# vl822.net
KiCad netlist of a schematic drawn in Altium Designer
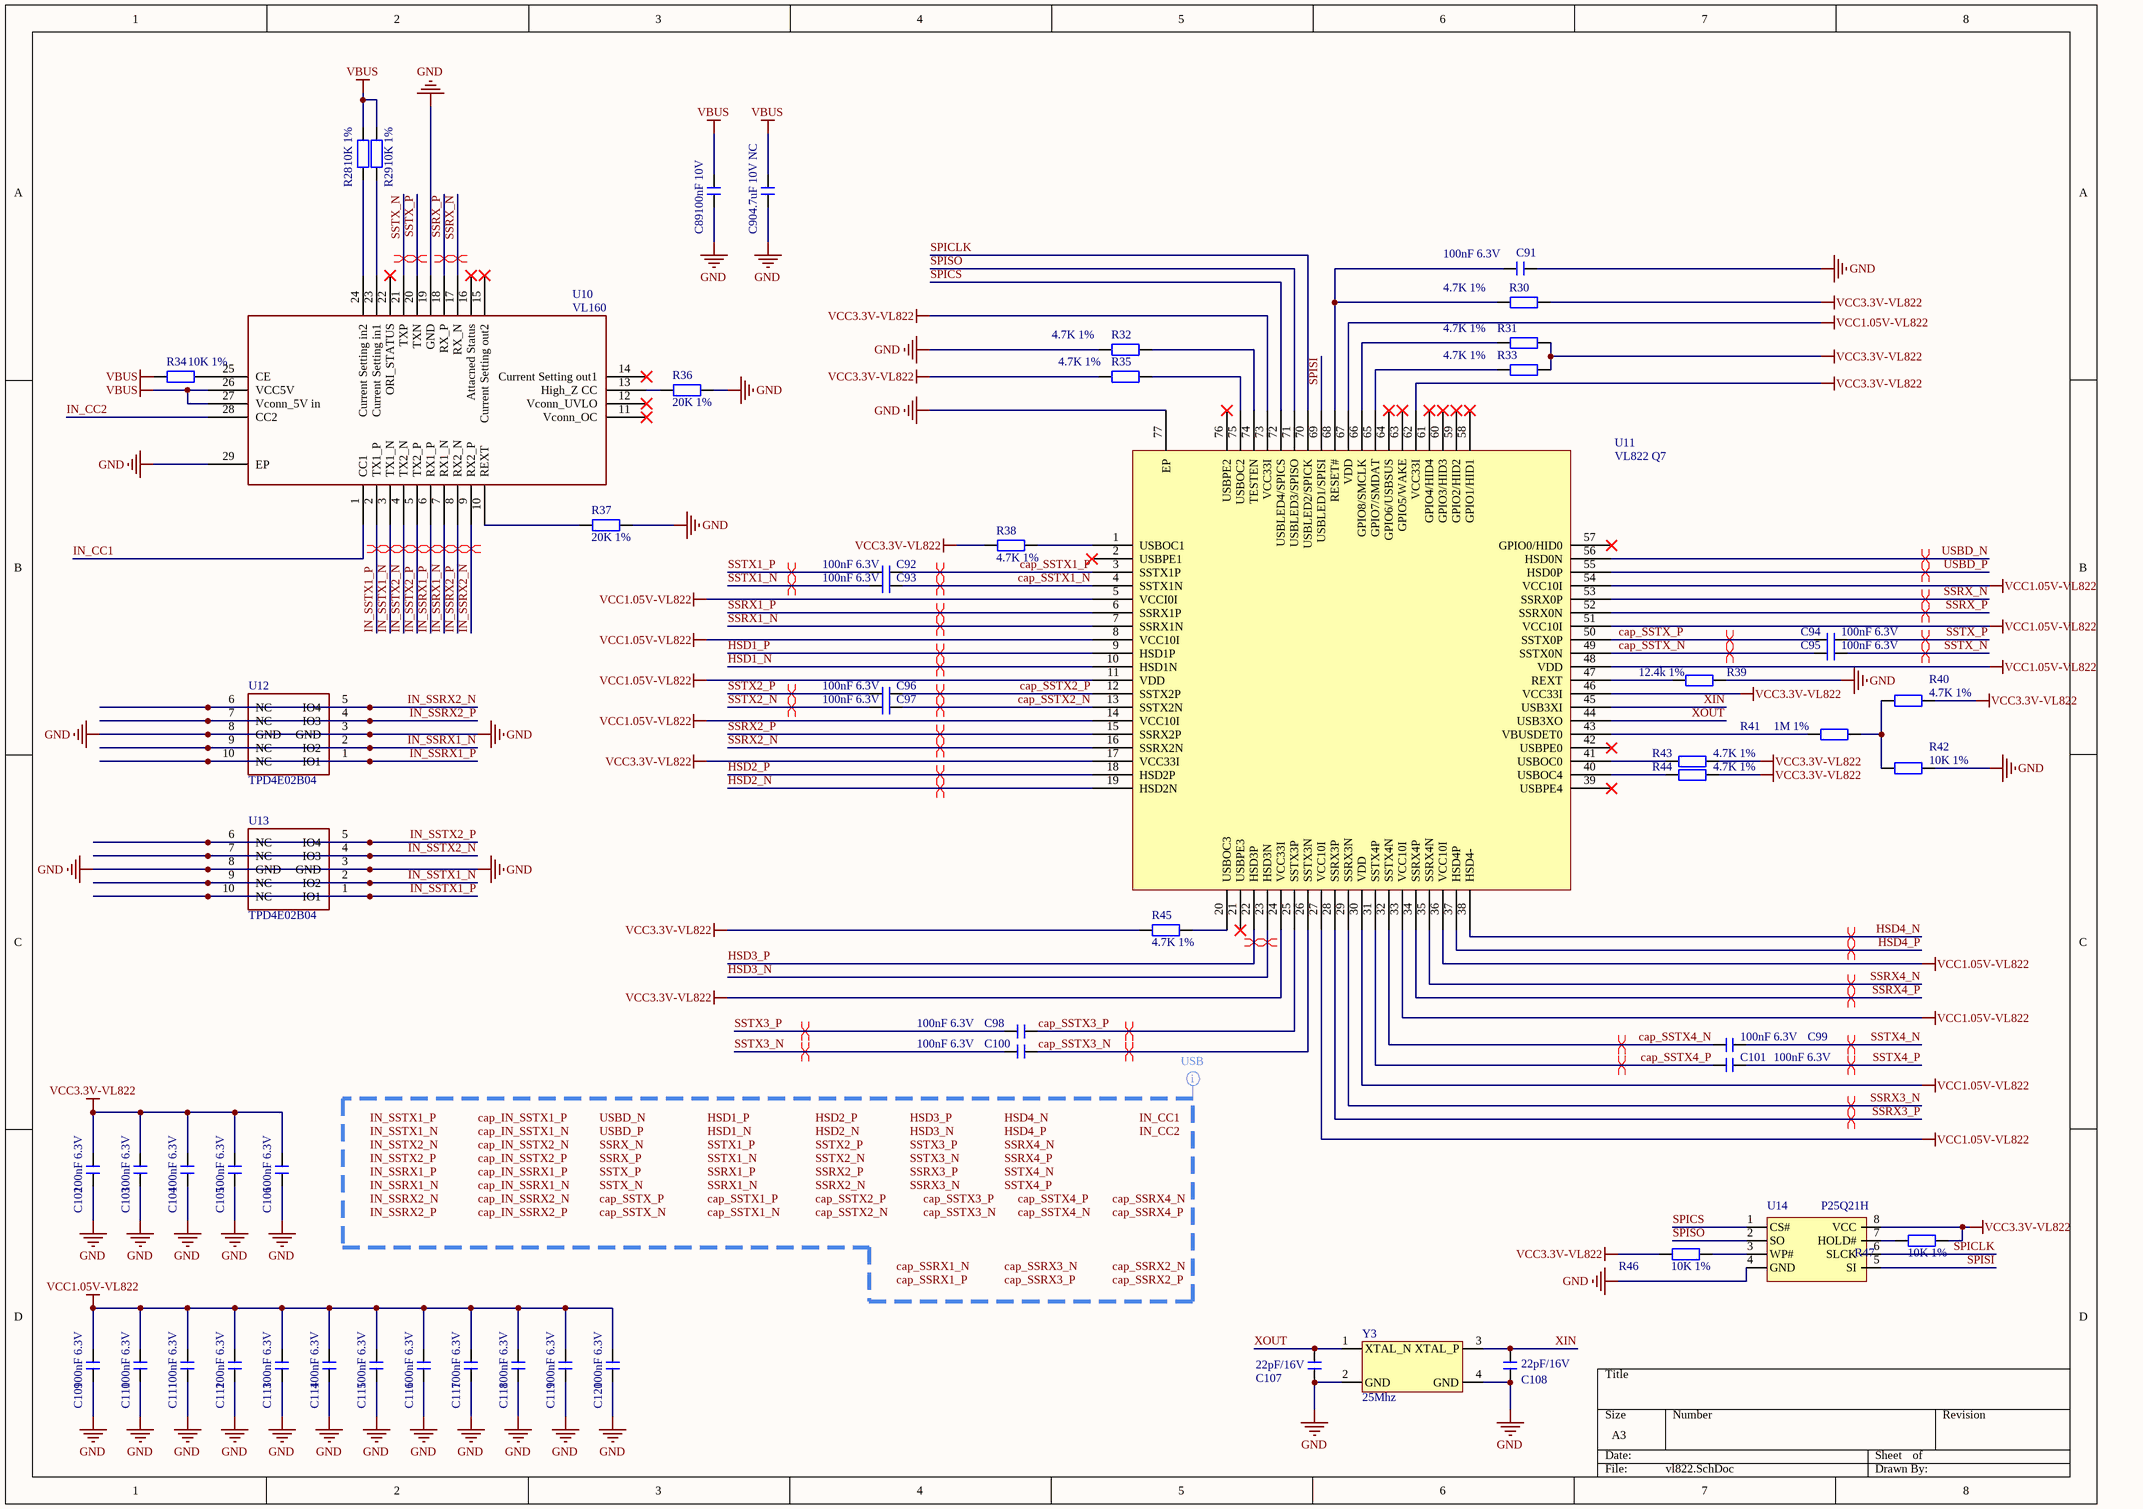
[diagram p0: vl822.SchDoc]

(export (version "E")
  (design (tool "Eeschema 10.0.6"))
  (components
    (comp (ref "C89")
      (value "100nF 10V")
      (footprint "C0402_L")
      (description "无极性贴片电容")
      (fields (field (name "版权归属") "源创客"))
      (libsource (lib "Capacitor") (part "C"))
    )
    (comp (ref "C90")
      (value "4.7uF 10V NC")
      (footprint "C0402_L")
      (description "无极性贴片电容")
      (fields (field (name "版权归属") "源创客"))
      (libsource (lib "Capacitor") (part "C"))
    )
    (comp (ref "C91")
      (value "100nF 6.3V")
      (footprint "C0402_L")
      (description "无极性贴片电容")
      (fields (field (name "版权归属") "源创客"))
      (libsource (lib "Capacitor") (part "C"))
    )
    (comp (ref "C92")
      (value "100nF 6.3V")
      (footprint "C0402_L")
      (description "无极性贴片电容")
      (fields (field (name "版权归属") "源创客"))
      (libsource (lib "Capacitor") (part "C"))
    )
    (comp (ref "C93")
      (value "100nF 6.3V")
      (footprint "C0402_L")
      (description "无极性贴片电容")
      (fields (field (name "版权归属") "源创客"))
      (libsource (lib "Capacitor") (part "C"))
    )
    (comp (ref "C94")
      (value "100nF 6.3V")
      (footprint "C0402_L")
      (description "无极性贴片电容")
      (fields (field (name "版权归属") "源创客"))
      (libsource (lib "Capacitor") (part "C"))
    )
    (comp (ref "C95")
      (value "100nF 6.3V")
      (footprint "C0402_L")
      (description "无极性贴片电容")
      (fields (field (name "版权归属") "源创客"))
      (libsource (lib "Capacitor") (part "C"))
    )
    (comp (ref "C96")
      (value "100nF 6.3V")
      (footprint "C0402_L")
      (description "无极性贴片电容")
      (fields (field (name "版权归属") "源创客"))
      (libsource (lib "Capacitor") (part "C"))
    )
    (comp (ref "C97")
      (value "100nF 6.3V")
      (footprint "C0402_L")
      (description "无极性贴片电容")
      (fields (field (name "版权归属") "源创客"))
      (libsource (lib "Capacitor") (part "C"))
    )
    (comp (ref "C98")
      (value "100nF 6.3V")
      (footprint "C0402_L")
      (description "无极性贴片电容")
      (fields (field (name "版权归属") "源创客"))
      (libsource (lib "Capacitor") (part "C"))
    )
    (comp (ref "C99")
      (value "100nF 6.3V")
      (footprint "C0402_L")
      (description "无极性贴片电容")
      (fields (field (name "版权归属") "源创客"))
      (libsource (lib "Capacitor") (part "C"))
    )
    (comp (ref "C100")
      (value "100nF 6.3V")
      (footprint "C0402_L")
      (description "无极性贴片电容")
      (fields (field (name "版权归属") "源创客"))
      (libsource (lib "Capacitor") (part "C"))
    )
    (comp (ref "C101")
      (value "100nF 6.3V")
      (footprint "C0402_L")
      (description "无极性贴片电容")
      (fields (field (name "版权归属") "源创客"))
      (libsource (lib "Capacitor") (part "C"))
    )
    (comp (ref "C102")
      (value "100nF 6.3V")
      (footprint "C0402_L")
      (description "无极性贴片电容")
      (fields (field (name "版权归属") "源创客"))
      (libsource (lib "Capacitor") (part "C"))
    )
    (comp (ref "C103")
      (value "100nF 6.3V")
      (footprint "C0402_L")
      (description "无极性贴片电容")
      (fields (field (name "版权归属") "源创客"))
      (libsource (lib "Capacitor") (part "C"))
    )
    (comp (ref "C104")
      (value "100nF 6.3V")
      (footprint "C0402_L")
      (description "无极性贴片电容")
      (fields (field (name "版权归属") "源创客"))
      (libsource (lib "Capacitor") (part "C"))
    )
    (comp (ref "C105")
      (value "100nF 6.3V")
      (footprint "C0402_L")
      (description "无极性贴片电容")
      (fields (field (name "版权归属") "源创客"))
      (libsource (lib "Capacitor") (part "C"))
    )
    (comp (ref "C106")
      (value "100nF 6.3V")
      (footprint "C0402_L")
      (description "无极性贴片电容")
      (fields (field (name "版权归属") "源创客"))
      (libsource (lib "Capacitor") (part "C"))
    )
    (comp (ref "C107")
      (value "22pF/16V")
      (footprint "C0402_L")
      (description "无极性贴片电容")
      (fields (field (name "版权归属") "源创客"))
      (libsource (lib "Capacitor") (part "C"))
    )
    (comp (ref "C108")
      (value "22pF/16V")
      (footprint "C0402_L")
      (description "无极性贴片电容")
      (fields (field (name "版权归属") "源创客"))
      (libsource (lib "Capacitor") (part "C"))
    )
    (comp (ref "C109")
      (value "100nF 6.3V")
      (footprint "C0402_L")
      (description "无极性贴片电容")
      (fields (field (name "版权归属") "源创客"))
      (libsource (lib "Capacitor") (part "C"))
    )
    (comp (ref "C110")
      (value "100nF 6.3V")
      (footprint "C0402_L")
      (description "无极性贴片电容")
      (fields (field (name "版权归属") "源创客"))
      (libsource (lib "Capacitor") (part "C"))
    )
    (comp (ref "C111")
      (value "100nF 6.3V")
      (footprint "C0402_L")
      (description "无极性贴片电容")
      (fields (field (name "版权归属") "源创客"))
      (libsource (lib "Capacitor") (part "C"))
    )
    (comp (ref "C112")
      (value "100nF 6.3V")
      (footprint "C0402_L")
      (description "无极性贴片电容")
      (fields (field (name "版权归属") "源创客"))
      (libsource (lib "Capacitor") (part "C"))
    )
    (comp (ref "C113")
      (value "100nF 6.3V")
      (footprint "C0402_L")
      (description "无极性贴片电容")
      (fields (field (name "版权归属") "源创客"))
      (libsource (lib "Capacitor") (part "C"))
    )
    (comp (ref "C114")
      (value "100nF 6.3V")
      (footprint "C0402_L")
      (description "无极性贴片电容")
      (fields (field (name "版权归属") "源创客"))
      (libsource (lib "Capacitor") (part "C"))
    )
    (comp (ref "C115")
      (value "100nF 6.3V")
      (footprint "C0402_L")
      (description "无极性贴片电容")
      (fields (field (name "版权归属") "源创客"))
      (libsource (lib "Capacitor") (part "C"))
    )
    (comp (ref "C116")
      (value "100nF 6.3V")
      (footprint "C0402_L")
      (description "无极性贴片电容")
      (fields (field (name "版权归属") "源创客"))
      (libsource (lib "Capacitor") (part "C"))
    )
    (comp (ref "C117")
      (value "100nF 6.3V")
      (footprint "C0402_L")
      (description "无极性贴片电容")
      (fields (field (name "版权归属") "源创客"))
      (libsource (lib "Capacitor") (part "C"))
    )
    (comp (ref "C118")
      (value "100nF 6.3V")
      (footprint "C0402_L")
      (description "无极性贴片电容")
      (fields (field (name "版权归属") "源创客"))
      (libsource (lib "Capacitor") (part "C"))
    )
    (comp (ref "C119")
      (value "100nF 6.3V")
      (footprint "C0402_L")
      (description "无极性贴片电容")
      (fields (field (name "版权归属") "源创客"))
      (libsource (lib "Capacitor") (part "C"))
    )
    (comp (ref "C120")
      (value "100nF 6.3V")
      (footprint "C0402_L")
      (description "无极性贴片电容")
      (fields (field (name "版权归属") "源创客"))
      (libsource (lib "Capacitor") (part "C"))
    )
    (comp (ref "R28")
      (value "10K 1%")
      (footprint "R0402_L")
      (description "贴片电阻")
      (fields (field (name "版权归属") "源创客"))
      (libsource (lib "Resistor") (part "R"))
    )
    (comp (ref "R29")
      (value "10K 1%")
      (footprint "R0402_L")
      (description "贴片电阻")
      (fields (field (name "版权归属") "源创客"))
      (libsource (lib "Resistor") (part "R"))
    )
    (comp (ref "R30")
      (value "4.7K 1%")
      (footprint "R0402_L")
      (description "贴片电阻")
      (fields (field (name "版权归属") "源创客"))
      (libsource (lib "Resistor") (part "R"))
    )
    (comp (ref "R31")
      (value "4.7K 1%")
      (footprint "R0402_L")
      (description "贴片电阻")
      (fields (field (name "版权归属") "源创客"))
      (libsource (lib "Resistor") (part "R"))
    )
    (comp (ref "R32")
      (value "4.7K 1%")
      (footprint "R0402_L")
      (description "贴片电阻")
      (fields (field (name "版权归属") "源创客"))
      (libsource (lib "Resistor") (part "R"))
    )
    (comp (ref "R33")
      (value "4.7K 1%")
      (footprint "R0402_L")
      (description "贴片电阻")
      (fields (field (name "版权归属") "源创客"))
      (libsource (lib "Resistor") (part "R"))
    )
    (comp (ref "R34")
      (value "10K 1%")
      (footprint "R0402_L")
      (description "贴片电阻")
      (fields (field (name "版权归属") "源创客"))
      (libsource (lib "Resistor") (part "R"))
    )
    (comp (ref "R35")
      (value "4.7K 1%")
      (footprint "R0402_L")
      (description "贴片电阻")
      (fields (field (name "版权归属") "源创客"))
      (libsource (lib "Resistor") (part "R"))
    )
    (comp (ref "R36")
      (value "20K 1%")
      (footprint "R0402_L")
      (description "贴片电阻")
      (fields (field (name "版权归属") "源创客"))
      (libsource (lib "Resistor") (part "R"))
    )
    (comp (ref "R37")
      (value "20K 1%")
      (footprint "R0402_L")
      (description "贴片电阻")
      (fields (field (name "版权归属") "源创客"))
      (libsource (lib "Resistor") (part "R"))
    )
    (comp (ref "R38")
      (value "4.7K 1%")
      (footprint "R0402_L")
      (description "贴片电阻")
      (fields (field (name "版权归属") "源创客"))
      (libsource (lib "Resistor") (part "R"))
    )
    (comp (ref "R39")
      (value "12.4k 1%")
      (footprint "R0402_L")
      (description "贴片电阻")
      (fields (field (name "版权归属") "源创客"))
      (libsource (lib "Resistor") (part "R"))
    )
    (comp (ref "R40")
      (value "4.7K 1%")
      (footprint "R0402_L")
      (description "贴片电阻")
      (fields (field (name "版权归属") "源创客"))
      (libsource (lib "Resistor") (part "R"))
    )
    (comp (ref "R41")
      (value "1M 1%")
      (footprint "R0402_L")
      (description "贴片电阻")
      (fields (field (name "版权归属") "源创客"))
      (libsource (lib "Resistor") (part "R"))
    )
    (comp (ref "R42")
      (value "10K 1%")
      (footprint "R0402_L")
      (description "贴片电阻")
      (fields (field (name "版权归属") "源创客"))
      (libsource (lib "Resistor") (part "R"))
    )
    (comp (ref "R43")
      (value "4.7K 1%")
      (footprint "R0402_L")
      (description "贴片电阻")
      (fields (field (name "版权归属") "源创客"))
      (libsource (lib "Resistor") (part "R"))
    )
    (comp (ref "R44")
      (value "4.7K 1%")
      (footprint "R0402_L")
      (description "贴片电阻")
      (fields (field (name "版权归属") "源创客"))
      (libsource (lib "Resistor") (part "R"))
    )
    (comp (ref "R45")
      (value "4.7K 1%")
      (footprint "R0402_L")
      (description "贴片电阻")
      (fields (field (name "版权归属") "源创客"))
      (libsource (lib "Resistor") (part "R"))
    )
    (comp (ref "R46")
      (value "10K 1%")
      (footprint "R0402_L")
      (description "贴片电阻")
      (fields (field (name "版权归属") "源创客"))
      (libsource (lib "Resistor") (part "R"))
    )
    (comp (ref "R47")
      (value "10K 1%")
      (footprint "R0402_L")
      (description "贴片电阻")
      (fields (field (name "版权归属") "源创客"))
      (libsource (lib "Resistor") (part "R"))
    )
    (comp (ref "U10")
      (value "VL160")
      (footprint "MQFN-28_L4.5-W3.5-P0.40-BL-EP")
      (libsource (lib "Brage") (part "VL160"))
    )
    (comp (ref "U11")
      (value "VL822 Q7")
      (footprint "QFN-76_L9.0-W9.0-P0.40-EP6.3-TL")
      (libsource (lib "Brage") (part "VL822 Q7"))
    )
    (comp (ref "U12")
      (value "TPD4E02B04")
      (footprint "DIO_TPD4E02B04DQAR")
      (description "ESD")
      (libsource (lib "Diode") (part "TPD4E02B04"))
    )
    (comp (ref "U13")
      (value "TPD4E02B04")
      (footprint "DIO_TPD4E02B04DQAR")
      (description "ESD")
      (libsource (lib "Diode") (part "TPD4E02B04"))
    )
    (comp (ref "U14") (value "P25Q21H") (footprint "SOP8_L") (libsource (lib "Flash") (part "P25D40H")))
    (comp (ref "Y3") (value "25Mhz") (footprint "OSC 3225-4P") (libsource (lib "Crystal") (part "Crystal")))
  )
  (nets
    (net (code "1") (name "/HSD1_N") (class "Default")
      (node (ref "U11") (pin "10") (pinfunction "HSD1N_10") (pintype "passive"))
    )
    (net (code "2") (name "/HSD1_P") (class "Default")
      (node (ref "U11") (pin "9") (pinfunction "HSD1P_9") (pintype "passive"))
    )
    (net (code "3") (name "/HSD2_N") (class "Default")
      (node (ref "U11") (pin "19") (pinfunction "HSD2N_19") (pintype "passive"))
    )
    (net (code "4") (name "/HSD2_P") (class "Default")
      (node (ref "U11") (pin "18") (pinfunction "HSD2P_18") (pintype "passive"))
    )
    (net (code "5") (name "/HSD3_N") (class "Default")
      (node (ref "U11") (pin "23") (pinfunction "HSD3N_23") (pintype "passive"))
    )
    (net (code "6") (name "/HSD3_P") (class "Default")
      (node (ref "U11") (pin "22") (pinfunction "HSD3P_22") (pintype "passive"))
    )
    (net (code "7") (name "/HSD4_N") (class "Default")
      (node (ref "U11") (pin "38") (pinfunction "HSD4-_38") (pintype "passive"))
    )
    (net (code "8") (name "/HSD4_P") (class "Default")
      (node (ref "U11") (pin "37") (pinfunction "HSD4P_37") (pintype "passive"))
    )
    (net (code "9") (name "/IN_CC1") (class "Default")
      (node (ref "U10") (pin "1") (pinfunction "CC1_1") (pintype "passive"))
    )
    (net (code "10") (name "/IN_CC2") (class "Default")
      (node (ref "U10") (pin "28") (pinfunction "CC2_28") (pintype "passive"))
    )
    (net (code "11") (name "/IN_SSRX1_N") (class "Default")
      (node (ref "U10") (pin "7") (pinfunction "RX1_N_7") (pintype "passive"))
      (node (ref "U12") (pin "2") (pinfunction "IO2_2") (pintype "passive"))
      (node (ref "U12") (pin "9") (pinfunction "NC_9") (pintype "passive"))
    )
    (net (code "12") (name "/IN_SSRX1_P") (class "Default")
      (node (ref "U10") (pin "6") (pinfunction "RX1_P_6") (pintype "passive"))
      (node (ref "U12") (pin "1") (pinfunction "IO1_1") (pintype "passive"))
      (node (ref "U12") (pin "10") (pinfunction "NC_10") (pintype "passive"))
    )
    (net (code "13") (name "/IN_SSRX2_N") (class "Default")
      (node (ref "U10") (pin "9") (pinfunction "RX2_P_9") (pintype "passive"))
      (node (ref "U12") (pin "5") (pinfunction "IO4_5") (pintype "passive"))
      (node (ref "U12") (pin "6") (pinfunction "NC_6") (pintype "passive"))
    )
    (net (code "14") (name "/IN_SSRX2_P") (class "Default")
      (node (ref "U10") (pin "8") (pinfunction "RX2_N_8") (pintype "passive"))
      (node (ref "U12") (pin "4") (pinfunction "IO3_4") (pintype "passive"))
      (node (ref "U12") (pin "7") (pinfunction "NC_7") (pintype "passive"))
    )
    (net (code "15") (name "/IN_SSTX1_N") (class "Default")
      (node (ref "U10") (pin "3") (pinfunction "TX1_N_3") (pintype "passive"))
      (node (ref "U13") (pin "2") (pinfunction "IO2_2") (pintype "passive"))
      (node (ref "U13") (pin "9") (pinfunction "NC_9") (pintype "passive"))
    )
    (net (code "16") (name "/IN_SSTX1_P") (class "Default")
      (node (ref "U10") (pin "2") (pinfunction "TX1_P_2") (pintype "passive"))
      (node (ref "U13") (pin "1") (pinfunction "IO1_1") (pintype "passive"))
      (node (ref "U13") (pin "10") (pinfunction "NC_10") (pintype "passive"))
    )
    (net (code "17") (name "/IN_SSTX2_N") (class "Default")
      (node (ref "U10") (pin "4") (pinfunction "TX2_N_4") (pintype "passive"))
      (node (ref "U13") (pin "4") (pinfunction "IO3_4") (pintype "passive"))
      (node (ref "U13") (pin "7") (pinfunction "NC_7") (pintype "passive"))
    )
    (net (code "18") (name "/IN_SSTX2_P") (class "Default")
      (node (ref "U10") (pin "5") (pinfunction "TX2_P_5") (pintype "passive"))
      (node (ref "U13") (pin "5") (pinfunction "IO4_5") (pintype "passive"))
      (node (ref "U13") (pin "6") (pinfunction "NC_6") (pintype "passive"))
    )
    (net (code "19") (name "/SPICLK") (class "Default")
      (node (ref "U11") (pin "70") (pinfunction "USBLED2/SPICK_70") (pintype "passive"))
      (node (ref "U14") (pin "6") (pinfunction "SLCK_6") (pintype "passive"))
    )
    (net (code "20") (name "/SPICS") (class "Default")
      (node (ref "U11") (pin "72") (pinfunction "USBLED4/SPICS_72") (pintype "passive"))
      (node (ref "U14") (pin "1") (pinfunction "CS#_1") (pintype "passive"))
    )
    (net (code "21") (name "/SPISI") (class "Default")
      (node (ref "U11") (pin "69") (pinfunction "USBLED1/SPISI_69") (pintype "passive"))
      (node (ref "U14") (pin "5") (pinfunction "SI_5") (pintype "passive"))
    )
    (net (code "22") (name "/SPISO") (class "Default")
      (node (ref "U11") (pin "71") (pinfunction "USBLED3/SPISO_71") (pintype "passive"))
      (node (ref "U14") (pin "2") (pinfunction "SO_2") (pintype "passive"))
    )
    (net (code "23") (name "/SSRX1_N") (class "Default")
      (node (ref "U11") (pin "7") (pinfunction "SSRX1N_7") (pintype "passive"))
    )
    (net (code "24") (name "/SSRX1_P") (class "Default")
      (node (ref "U11") (pin "6") (pinfunction "SSRX1P_6") (pintype "passive"))
    )
    (net (code "25") (name "/SSRX2_N") (class "Default")
      (node (ref "U11") (pin "16") (pinfunction "SSRX2N_16") (pintype "passive"))
    )
    (net (code "26") (name "/SSRX2_P") (class "Default")
      (node (ref "U11") (pin "15") (pinfunction "SSRX2P_15") (pintype "passive"))
    )
    (net (code "27") (name "/SSRX3_N") (class "Default")
      (node (ref "U11") (pin "29") (pinfunction "SSRX3N_29") (pintype "passive"))
    )
    (net (code "28") (name "/SSRX3_P") (class "Default")
      (node (ref "U11") (pin "28") (pinfunction "SSRX3P_28") (pintype "passive"))
    )
    (net (code "29") (name "/SSRX4_N") (class "Default")
      (node (ref "U11") (pin "35") (pinfunction "SSRX4N_35") (pintype "passive"))
    )
    (net (code "30") (name "/SSRX4_P") (class "Default")
      (node (ref "U11") (pin "34") (pinfunction "SSRX4P_34") (pintype "passive"))
    )
    (net (code "31") (name "/SSRX_N") (class "Default")
      (node (ref "U10") (pin "17") (pinfunction "RX_N_17") (pintype "passive"))
      (node (ref "U11") (pin "53") (pinfunction "SSRX0P_53") (pintype "passive"))
    )
    (net (code "32") (name "/SSRX_P") (class "Default")
      (node (ref "U10") (pin "18") (pinfunction "RX_P_18") (pintype "passive"))
      (node (ref "U11") (pin "52") (pinfunction "SSRX0N_52") (pintype "passive"))
    )
    (net (code "33") (name "/SSTX1_N") (class "Default")
      (node (ref "C93") (pin "1") (pinfunction "1_1") (pintype "passive"))
    )
    (net (code "34") (name "/SSTX1_P") (class "Default")
      (node (ref "C92") (pin "1") (pinfunction "1_1") (pintype "passive"))
    )
    (net (code "35") (name "/SSTX2_N") (class "Default")
      (node (ref "C97") (pin "1") (pinfunction "1_1") (pintype "passive"))
    )
    (net (code "36") (name "/SSTX2_P") (class "Default")
      (node (ref "C96") (pin "1") (pinfunction "1_1") (pintype "passive"))
    )
    (net (code "37") (name "/SSTX3_N") (class "Default")
      (node (ref "C100") (pin "1") (pinfunction "1_1") (pintype "passive"))
    )
    (net (code "38") (name "/SSTX3_P") (class "Default")
      (node (ref "C98") (pin "1") (pinfunction "1_1") (pintype "passive"))
    )
    (net (code "39") (name "/SSTX4_N") (class "Default")
      (node (ref "C99") (pin "1") (pinfunction "1_1") (pintype "passive"))
    )
    (net (code "40") (name "/SSTX4_P") (class "Default")
      (node (ref "C101") (pin "1") (pinfunction "1_1") (pintype "passive"))
    )
    (net (code "41") (name "/SSTX_N") (class "Default")
      (node (ref "C95") (pin "1") (pinfunction "1_1") (pintype "passive"))
      (node (ref "U10") (pin "21") (pinfunction "TXP_21") (pintype "passive"))
    )
    (net (code "42") (name "/SSTX_P") (class "Default")
      (node (ref "C94") (pin "1") (pinfunction "1_1") (pintype "passive"))
      (node (ref "U10") (pin "20") (pinfunction "TXN_20") (pintype "passive"))
    )
    (net (code "43") (name "/USBD_N") (class "Default")
      (node (ref "U11") (pin "56") (pinfunction "HSD0N_56") (pintype "passive"))
    )
    (net (code "44") (name "/USBD_P") (class "Default")
      (node (ref "U11") (pin "55") (pinfunction "HSD0P_55") (pintype "passive"))
    )
    (net (code "45") (name "/XIN") (class "Default")
      (node (ref "C108") (pin "1") (pinfunction "1_1") (pintype "passive"))
      (node (ref "U11") (pin "45") (pinfunction "USB3XI_45") (pintype "passive"))
      (node (ref "Y3") (pin "3") (pinfunction "XTAL_P_3") (pintype "passive"))
    )
    (net (code "46") (name "/XOUT") (class "Default")
      (node (ref "C107") (pin "1") (pinfunction "1_1") (pintype "passive"))
      (node (ref "U11") (pin "44") (pinfunction "USB3XO_44") (pintype "passive"))
      (node (ref "Y3") (pin "1") (pinfunction "XTAL_N_1") (pintype "passive"))
    )
    (net (code "63") (name "/cap_SSTX1_N") (class "Default")
      (node (ref "C93") (pin "2") (pinfunction "2_2") (pintype "passive"))
      (node (ref "U11") (pin "4") (pinfunction "SSTX1N_4") (pintype "passive"))
    )
    (net (code "64") (name "/cap_SSTX1_P") (class "Default")
      (node (ref "C92") (pin "2") (pinfunction "2_2") (pintype "passive"))
      (node (ref "U11") (pin "3") (pinfunction "SSTX1P_3") (pintype "passive"))
    )
    (net (code "65") (name "/cap_SSTX2_N") (class "Default")
      (node (ref "C97") (pin "2") (pinfunction "2_2") (pintype "passive"))
      (node (ref "U11") (pin "13") (pinfunction "SSTX2N_13") (pintype "passive"))
    )
    (net (code "66") (name "/cap_SSTX2_P") (class "Default")
      (node (ref "C96") (pin "2") (pinfunction "2_2") (pintype "passive"))
      (node (ref "U11") (pin "12") (pinfunction "SSTX2P_12") (pintype "passive"))
    )
    (net (code "67") (name "/cap_SSTX3_N") (class "Default")
      (node (ref "C100") (pin "2") (pinfunction "2_2") (pintype "passive"))
      (node (ref "U11") (pin "26") (pinfunction "SSTX3N_26") (pintype "passive"))
    )
    (net (code "68") (name "/cap_SSTX3_P") (class "Default")
      (node (ref "C98") (pin "2") (pinfunction "2_2") (pintype "passive"))
      (node (ref "U11") (pin "25") (pinfunction "SSTX3P_25") (pintype "passive"))
    )
    (net (code "69") (name "/cap_SSTX4_N") (class "Default")
      (node (ref "C99") (pin "2") (pinfunction "2_2") (pintype "passive"))
      (node (ref "U11") (pin "32") (pinfunction "SSTX4N_32") (pintype "passive"))
    )
    (net (code "70") (name "/cap_SSTX4_P") (class "Default")
      (node (ref "C101") (pin "2") (pinfunction "2_2") (pintype "passive"))
      (node (ref "U11") (pin "31") (pinfunction "SSTX4P_31") (pintype "passive"))
    )
    (net (code "71") (name "/cap_SSTX_N") (class "Default")
      (node (ref "C95") (pin "2") (pinfunction "2_2") (pintype "passive"))
      (node (ref "U11") (pin "49") (pinfunction "SSTX0N_49") (pintype "passive"))
    )
    (net (code "72") (name "/cap_SSTX_P") (class "Default")
      (node (ref "C94") (pin "2") (pinfunction "2_2") (pintype "passive"))
      (node (ref "U11") (pin "50") (pinfunction "SSTX0P_50") (pintype "passive"))
    )
    (net (code "73") (name "GND") (class "Default")
      (node (ref "C102") (pin "1") (pinfunction "1_1") (pintype "passive"))
      (node (ref "C103") (pin "1") (pinfunction "1_1") (pintype "passive"))
      (node (ref "C104") (pin "1") (pinfunction "1_1") (pintype "passive"))
      (node (ref "C105") (pin "1") (pinfunction "1_1") (pintype "passive"))
      (node (ref "C106") (pin "1") (pinfunction "1_1") (pintype "passive"))
      (node (ref "C107") (pin "2") (pinfunction "2_2") (pintype "passive"))
      (node (ref "C108") (pin "2") (pinfunction "2_2") (pintype "passive"))
      (node (ref "C109") (pin "1") (pinfunction "1_1") (pintype "passive"))
      (node (ref "C110") (pin "1") (pinfunction "1_1") (pintype "passive"))
      (node (ref "C111") (pin "1") (pinfunction "1_1") (pintype "passive"))
      (node (ref "C112") (pin "1") (pinfunction "1_1") (pintype "passive"))
      (node (ref "C113") (pin "1") (pinfunction "1_1") (pintype "passive"))
      (node (ref "C114") (pin "1") (pinfunction "1_1") (pintype "passive"))
      (node (ref "C115") (pin "1") (pinfunction "1_1") (pintype "passive"))
      (node (ref "C116") (pin "1") (pinfunction "1_1") (pintype "passive"))
      (node (ref "C117") (pin "1") (pinfunction "1_1") (pintype "passive"))
      (node (ref "C118") (pin "1") (pinfunction "1_1") (pintype "passive"))
      (node (ref "C119") (pin "1") (pinfunction "1_1") (pintype "passive"))
      (node (ref "C120") (pin "1") (pinfunction "1_1") (pintype "passive"))
      (node (ref "C89") (pin "1") (pinfunction "1_1") (pintype "passive"))
      (node (ref "C90") (pin "1") (pinfunction "1_1") (pintype "passive"))
      (node (ref "C91") (pin "2") (pinfunction "2_2") (pintype "passive"))
      (node (ref "R32") (pin "2") (pinfunction "2_2") (pintype "passive"))
      (node (ref "R36") (pin "1") (pinfunction "1_1") (pintype "passive"))
      (node (ref "R37") (pin "1") (pinfunction "1_1") (pintype "passive"))
      (node (ref "R39") (pin "2") (pinfunction "2_2") (pintype "passive"))
      (node (ref "R42") (pin "2") (pinfunction "2_2") (pintype "passive"))
      (node (ref "U10") (pin "19") (pinfunction "GND_19") (pintype "passive"))
      (node (ref "U10") (pin "29") (pinfunction "EP_29") (pintype "passive"))
      (node (ref "U11") (pin "77") (pinfunction "EP_77") (pintype "passive"))
      (node (ref "U12") (pin "3") (pinfunction "GND_3") (pintype "passive"))
      (node (ref "U12") (pin "8") (pinfunction "GND_8") (pintype "passive"))
      (node (ref "U13") (pin "3") (pinfunction "GND_3") (pintype "passive"))
      (node (ref "U13") (pin "8") (pinfunction "GND_8") (pintype "passive"))
      (node (ref "U14") (pin "4") (pinfunction "GND_4") (pintype "passive"))
      (node (ref "Y3") (pin "2") (pinfunction "GND_2") (pintype "passive"))
      (node (ref "Y3") (pin "4") (pinfunction "GND_4") (pintype "passive"))
    )
    (net (code "74") (name "Net-(R40-Pad1)") (class "Default")
      (node (ref "R40") (pin "1") (pinfunction "1_1") (pintype "passive"))
      (node (ref "R41") (pin "2") (pinfunction "2_2") (pintype "passive"))
      (node (ref "R42") (pin "1") (pinfunction "1_1") (pintype "passive"))
    )
    (net (code "75") (name "Net-(U10-CE)") (class "Default")
      (node (ref "R34") (pin "1") (pinfunction "1_1") (pintype "passive"))
      (node (ref "U10") (pin "25") (pinfunction "CE_25") (pintype "passive"))
    )
    (net (code "76") (name "Net-(U10-Current_Setting_in1)") (class "Default")
      (node (ref "R29") (pin "2") (pinfunction "2_2") (pintype "passive"))
      (node (ref "U10") (pin "23") (pinfunction "Current_Setting_in1_23") (pintype "passive"))
    )
    (net (code "77") (name "Net-(U10-Current_Setting_in2)") (class "Default")
      (node (ref "R28") (pin "2") (pinfunction "2_2") (pintype "passive"))
      (node (ref "U10") (pin "24") (pinfunction "Current_Setting_in2_24") (pintype "passive"))
    )
    (net (code "78") (name "Net-(U10-High_Z_CC)") (class "Default")
      (node (ref "R36") (pin "2") (pinfunction "2_2") (pintype "passive"))
      (node (ref "U10") (pin "13") (pinfunction "High_Z_CC_13") (pintype "passive"))
    )
    (net (code "79") (name "Net-(U10-REXT)") (class "Default")
      (node (ref "R37") (pin "2") (pinfunction "2_2") (pintype "passive"))
      (node (ref "U10") (pin "10") (pinfunction "REXT_10") (pintype "passive"))
    )
    (net (code "80") (name "Net-(U11-GPIO7{slash}SMDAT)") (class "Default")
      (node (ref "R33") (pin "1") (pinfunction "1_1") (pintype "passive"))
      (node (ref "U11") (pin "65") (pinfunction "GPIO7/SMDAT_65") (pintype "passive"))
    )
    (net (code "81") (name "Net-(U11-GPIO8{slash}SMCLK)") (class "Default")
      (node (ref "R31") (pin "1") (pinfunction "1_1") (pintype "passive"))
      (node (ref "U11") (pin "66") (pinfunction "GPIO8/SMCLK_66") (pintype "passive"))
    )
    (net (code "82") (name "Net-(U11-RESET#)") (class "Default")
      (node (ref "C91") (pin "1") (pinfunction "1_1") (pintype "passive"))
      (node (ref "R30") (pin "1") (pinfunction "1_1") (pintype "passive"))
      (node (ref "U11") (pin "68") (pinfunction "RESET#_68") (pintype "passive"))
    )
    (net (code "83") (name "Net-(U11-REXT)") (class "Default")
      (node (ref "R39") (pin "1") (pinfunction "1_1") (pintype "passive"))
      (node (ref "U11") (pin "47") (pinfunction "REXT_47") (pintype "passive"))
    )
    (net (code "84") (name "Net-(U11-TESTEN)") (class "Default")
      (node (ref "R32") (pin "1") (pinfunction "1_1") (pintype "passive"))
      (node (ref "U11") (pin "74") (pinfunction "TESTEN_74") (pintype "passive"))
    )
    (net (code "85") (name "Net-(U11-USBOC0)") (class "Default")
      (node (ref "R43") (pin "1") (pinfunction "1_1") (pintype "passive"))
      (node (ref "U11") (pin "41") (pinfunction "USBOC0_41") (pintype "passive"))
    )
    (net (code "86") (name "Net-(U11-USBOC1)") (class "Default")
      (node (ref "R38") (pin "1") (pinfunction "1_1") (pintype "passive"))
      (node (ref "U11") (pin "1") (pinfunction "USBOC1_1") (pintype "passive"))
    )
    (net (code "87") (name "Net-(U11-USBOC2)") (class "Default")
      (node (ref "R35") (pin "1") (pinfunction "1_1") (pintype "passive"))
      (node (ref "U11") (pin "75") (pinfunction "USBOC2_75") (pintype "passive"))
    )
    (net (code "88") (name "Net-(U11-USBOC3)") (class "Default")
      (node (ref "R45") (pin "1") (pinfunction "1_1") (pintype "passive"))
      (node (ref "U11") (pin "20") (pinfunction "USBOC3_20") (pintype "passive"))
    )
    (net (code "89") (name "Net-(U11-USBOC4)") (class "Default")
      (node (ref "R44") (pin "1") (pinfunction "1_1") (pintype "passive"))
      (node (ref "U11") (pin "40") (pinfunction "USBOC4_40") (pintype "passive"))
    )
    (net (code "90") (name "Net-(U11-VBUSDET0)") (class "Default")
      (node (ref "R41") (pin "1") (pinfunction "1_1") (pintype "passive"))
      (node (ref "U11") (pin "43") (pinfunction "VBUSDET0_43") (pintype "passive"))
    )
    (net (code "91") (name "Net-(U14-HOLD#)") (class "Default")
      (node (ref "R47") (pin "2") (pinfunction "2_2") (pintype "passive"))
      (node (ref "U14") (pin "7") (pinfunction "HOLD#_7") (pintype "passive"))
    )
    (net (code "92") (name "Net-(U14-WP#)") (class "Default")
      (node (ref "R46") (pin "1") (pinfunction "1_1") (pintype "passive"))
      (node (ref "U14") (pin "3") (pinfunction "WP#_3") (pintype "passive"))
    )
    (net (code "93") (name "VBUS") (class "Default")
      (node (ref "C89") (pin "2") (pinfunction "2_2") (pintype "passive"))
      (node (ref "C90") (pin "2") (pinfunction "2_2") (pintype "passive"))
      (node (ref "R28") (pin "1") (pinfunction "1_1") (pintype "passive"))
      (node (ref "R29") (pin "1") (pinfunction "1_1") (pintype "passive"))
      (node (ref "R34") (pin "2") (pinfunction "2_2") (pintype "passive"))
      (node (ref "U10") (pin "26") (pinfunction "VCC5V_26") (pintype "passive"))
      (node (ref "U10") (pin "27") (pinfunction "Vconn_5V_in_27") (pintype "passive"))
    )
    (net (code "94") (name "VCC1.05V-VL822") (class "Default")
      (node (ref "C109") (pin "2") (pinfunction "2_2") (pintype "passive"))
      (node (ref "C110") (pin "2") (pinfunction "2_2") (pintype "passive"))
      (node (ref "C111") (pin "2") (pinfunction "2_2") (pintype "passive"))
      (node (ref "C112") (pin "2") (pinfunction "2_2") (pintype "passive"))
      (node (ref "C113") (pin "2") (pinfunction "2_2") (pintype "passive"))
      (node (ref "C114") (pin "2") (pinfunction "2_2") (pintype "passive"))
      (node (ref "C115") (pin "2") (pinfunction "2_2") (pintype "passive"))
      (node (ref "C116") (pin "2") (pinfunction "2_2") (pintype "passive"))
      (node (ref "C117") (pin "2") (pinfunction "2_2") (pintype "passive"))
      (node (ref "C118") (pin "2") (pinfunction "2_2") (pintype "passive"))
      (node (ref "C119") (pin "2") (pinfunction "2_2") (pintype "passive"))
      (node (ref "C120") (pin "2") (pinfunction "2_2") (pintype "passive"))
      (node (ref "U11") (pin "11") (pinfunction "VDD_11") (pintype "passive"))
      (node (ref "U11") (pin "14") (pinfunction "VCC10I_14") (pintype "passive"))
      (node (ref "U11") (pin "27") (pinfunction "VCC10I_27") (pintype "passive"))
      (node (ref "U11") (pin "30") (pinfunction "VDD_30") (pintype "passive"))
      (node (ref "U11") (pin "33") (pinfunction "VCC10I_33") (pintype "passive"))
      (node (ref "U11") (pin "36") (pinfunction "VCC10I_36") (pintype "passive"))
      (node (ref "U11") (pin "48") (pinfunction "VDD_48") (pintype "passive"))
      (node (ref "U11") (pin "5") (pinfunction "VCCI0I_5") (pintype "passive"))
      (node (ref "U11") (pin "51") (pinfunction "VCC10I_51") (pintype "passive"))
      (node (ref "U11") (pin "54") (pinfunction "VCC10I_54") (pintype "passive"))
      (node (ref "U11") (pin "67") (pinfunction "VDD_67") (pintype "passive"))
      (node (ref "U11") (pin "8") (pinfunction "VCC10I_8") (pintype "passive"))
    )
    (net (code "95") (name "VCC3.3V-VL822") (class "Default")
      (node (ref "C102") (pin "2") (pinfunction "2_2") (pintype "passive"))
      (node (ref "C103") (pin "2") (pinfunction "2_2") (pintype "passive"))
      (node (ref "C104") (pin "2") (pinfunction "2_2") (pintype "passive"))
      (node (ref "C105") (pin "2") (pinfunction "2_2") (pintype "passive"))
      (node (ref "C106") (pin "2") (pinfunction "2_2") (pintype "passive"))
      (node (ref "R30") (pin "2") (pinfunction "2_2") (pintype "passive"))
      (node (ref "R31") (pin "2") (pinfunction "2_2") (pintype "passive"))
      (node (ref "R33") (pin "2") (pinfunction "2_2") (pintype "passive"))
      (node (ref "R35") (pin "2") (pinfunction "2_2") (pintype "passive"))
      (node (ref "R38") (pin "2") (pinfunction "2_2") (pintype "passive"))
      (node (ref "R40") (pin "2") (pinfunction "2_2") (pintype "passive"))
      (node (ref "R43") (pin "2") (pinfunction "2_2") (pintype "passive"))
      (node (ref "R44") (pin "2") (pinfunction "2_2") (pintype "passive"))
      (node (ref "R45") (pin "2") (pinfunction "2_2") (pintype "passive"))
      (node (ref "R46") (pin "2") (pinfunction "2_2") (pintype "passive"))
      (node (ref "R47") (pin "1") (pinfunction "1_1") (pintype "passive"))
      (node (ref "U11") (pin "17") (pinfunction "VCC33I_17") (pintype "passive"))
      (node (ref "U11") (pin "24") (pinfunction "VCC33I_24") (pintype "passive"))
      (node (ref "U11") (pin "46") (pinfunction "VCC33I_46") (pintype "passive"))
      (node (ref "U11") (pin "62") (pinfunction "VCC33I_62") (pintype "passive"))
      (node (ref "U11") (pin "73") (pinfunction "VCC33I_73") (pintype "passive"))
      (node (ref "U14") (pin "8") (pinfunction "VCC_8") (pintype "passive"))
    )
    (net (code "96") (name "unconnected-(U10-Attacned_Status-Pad16)") (class "Default")
      (node (ref "U10") (pin "16") (pinfunction "Attacned_Status_16") (pintype "passive+no_connect"))
    )
    (net (code "97") (name "unconnected-(U10-Current_Setting_out1-Pad14)") (class "Default")
      (node (ref "U10") (pin "14") (pinfunction "Current_Setting_out1_14") (pintype "passive+no_connect"))
    )
    (net (code "98") (name "unconnected-(U10-Current_Setting_out2-Pad15)") (class "Default")
      (node (ref "U10") (pin "15") (pinfunction "Current_Setting_out2_15") (pintype "passive+no_connect"))
    )
    (net (code "99") (name "unconnected-(U10-ORI_STATUS-Pad22)") (class "Default")
      (node (ref "U10") (pin "22") (pinfunction "ORI_STATUS_22") (pintype "passive+no_connect"))
    )
    (net (code "100") (name "unconnected-(U10-Vconn_OC-Pad11)") (class "Default")
      (node (ref "U10") (pin "11") (pinfunction "Vconn_OC_11") (pintype "passive+no_connect"))
    )
    (net (code "101") (name "unconnected-(U10-Vconn_UVLO-Pad12)") (class "Default")
      (node (ref "U10") (pin "12") (pinfunction "Vconn_UVLO_12") (pintype "passive+no_connect"))
    )
    (net (code "102") (name "unconnected-(U11-GPIO0{slash}HID0-Pad57)") (class "Default")
      (node (ref "U11") (pin "57") (pinfunction "GPIO0/HID0_57") (pintype "passive+no_connect"))
    )
    (net (code "103") (name "unconnected-(U11-GPIO1{slash}HID1-Pad58)") (class "Default")
      (node (ref "U11") (pin "58") (pinfunction "GPIO1/HID1_58") (pintype "passive+no_connect"))
    )
    (net (code "104") (name "unconnected-(U11-GPIO2{slash}HID2-Pad59)") (class "Default")
      (node (ref "U11") (pin "59") (pinfunction "GPIO2/HID2_59") (pintype "passive+no_connect"))
    )
    (net (code "105") (name "unconnected-(U11-GPIO3{slash}HID3-Pad60)") (class "Default")
      (node (ref "U11") (pin "60") (pinfunction "GPIO3/HID3_60") (pintype "passive+no_connect"))
    )
    (net (code "106") (name "unconnected-(U11-GPIO4{slash}HID4-Pad61)") (class "Default")
      (node (ref "U11") (pin "61") (pinfunction "GPIO4/HID4_61") (pintype "passive+no_connect"))
    )
    (net (code "107") (name "unconnected-(U11-GPIO5{slash}WAKE-Pad63)") (class "Default")
      (node (ref "U11") (pin "63") (pinfunction "GPIO5/WAKE_63") (pintype "passive+no_connect"))
    )
    (net (code "108") (name "unconnected-(U11-GPIO6{slash}USBSUS-Pad64)") (class "Default")
      (node (ref "U11") (pin "64") (pinfunction "GPIO6/USBSUS_64") (pintype "passive+no_connect"))
    )
    (net (code "109") (name "unconnected-(U11-USBPE0-Pad42)") (class "Default")
      (node (ref "U11") (pin "42") (pinfunction "USBPE0_42") (pintype "passive+no_connect"))
    )
    (net (code "110") (name "unconnected-(U11-USBPE1-Pad2)") (class "Default")
      (node (ref "U11") (pin "2") (pinfunction "USBPE1_2") (pintype "passive+no_connect"))
    )
    (net (code "111") (name "unconnected-(U11-USBPE2-Pad76)") (class "Default")
      (node (ref "U11") (pin "76") (pinfunction "USBPE2_76") (pintype "passive+no_connect"))
    )
    (net (code "112") (name "unconnected-(U11-USBPE3-Pad21)") (class "Default")
      (node (ref "U11") (pin "21") (pinfunction "USBPE3_21") (pintype "passive+no_connect"))
    )
    (net (code "113") (name "unconnected-(U11-USBPE4-Pad39)") (class "Default")
      (node (ref "U11") (pin "39") (pinfunction "USBPE4_39") (pintype "passive+no_connect"))
    )
  )
)
